# motor-control.net
KiCad netlist of a schematic drawn in Altium Designer
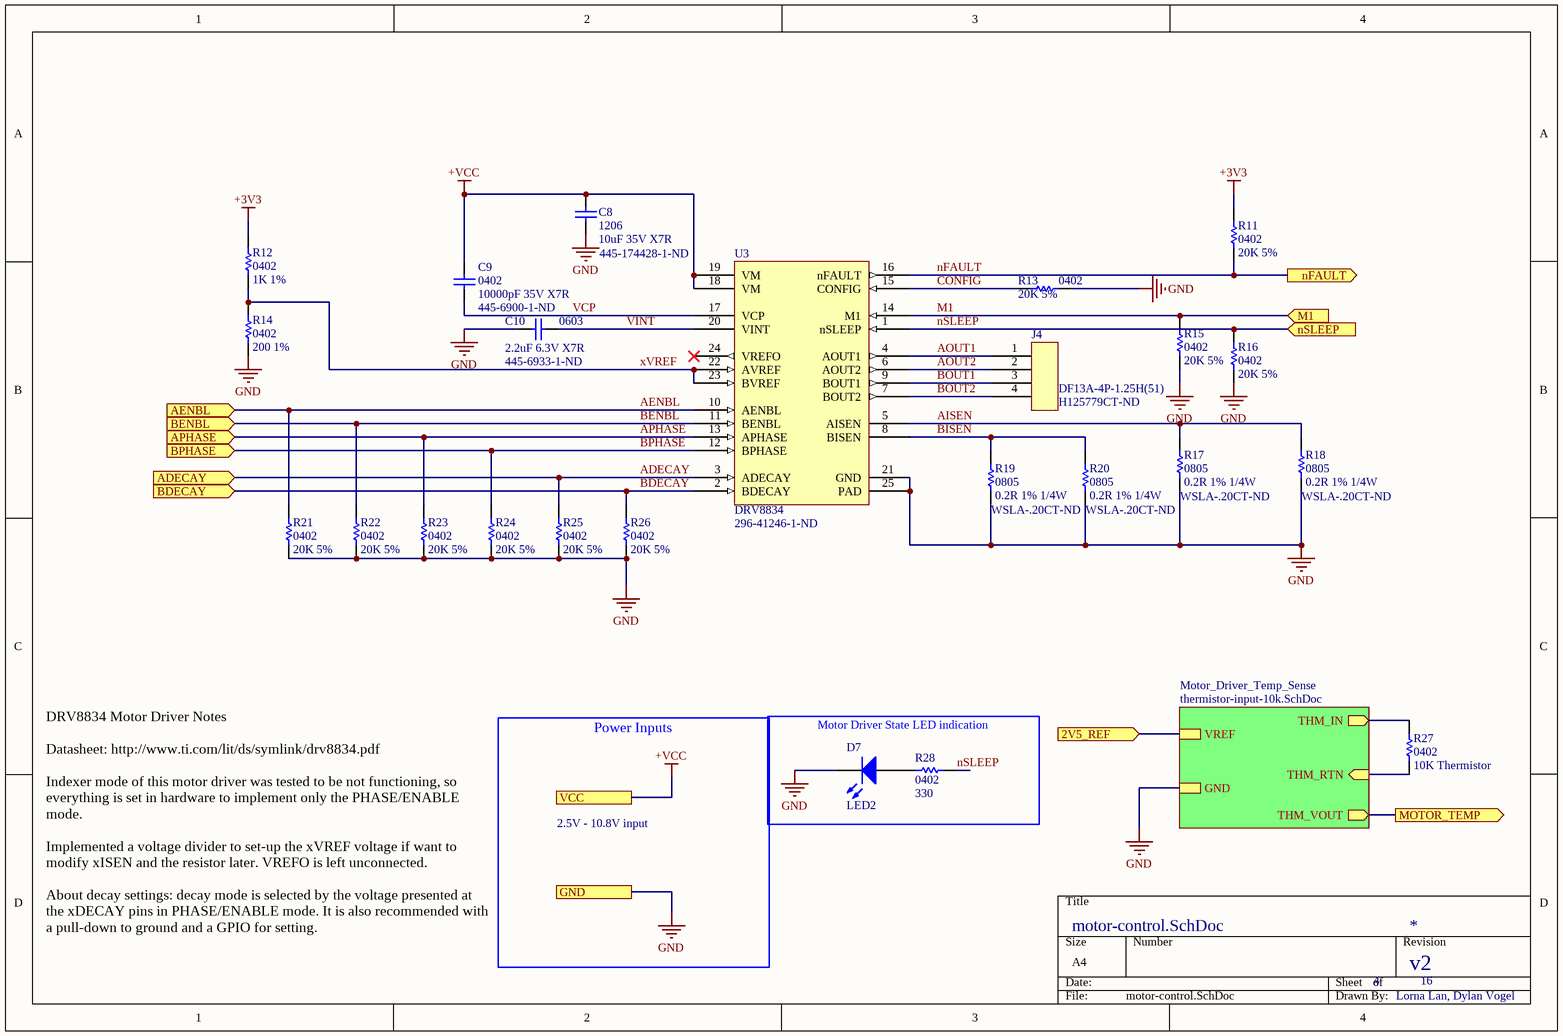
[diagram p0: motor-control.SchDoc]

(export (version "E")
  (design (tool "Eeschema 10.0.6"))
  (components
    (comp (ref "C8")
      (value "1206")
      (footprint "CAP1206R")
      (description "1206 capacitor")
      (fields
        (field (name "ALTIUM_VALUE") "10uF 35V X7R")
        (field (name "SUPPLIER PART NUMBER 1") "445-174428-1-ND")
      )
      (libsource (lib "CAP1206") (part "CAP1206"))
    )
    (comp (ref "C9")
      (value "0402")
      (footprint "CAP0402R")
      (description "0402 capacitor")
      (fields
        (field (name "ALTIUM_VALUE") "10000pF 35V X7R")
        (field (name "SUPPLIER PART NUMBER 1") "445-6900-1-ND")
      )
      (libsource (lib "CAP0402") (part "CAP0402"))
    )
    (comp (ref "C10")
      (value "0603")
      (footprint "CAP0603R")
      (description "0603 capacitor")
      (fields
        (field (name "ALTIUM_VALUE") "2.2uF 6.3V X7R")
        (field (name "SUPPLIER PART NUMBER 1") "445-6933-1-ND")
      )
      (libsource (lib "CAP0603") (part "CAP0603"))
    )
    (comp (ref "D7")
      (value "LED2")
      (footprint "0603-LED")
      (description "Typical RED, GREEN, YELLOW, AMBER GaAs LED")
      (fields (field (name "PUBLISHER") "Altium Limited"))
      (libsource (lib "Miscellaneous Devices") (part "LED2"))
    )
    (comp (ref "J4")
      (value "DF13A-4P-1.25H(51)")
      (footprint "DF13A-4P-1.25H(51)")
      (description "4 pos DF13 right angle surface mount connector")
      (fields (field (name "SUPPLIER PART NUMBER 1") "H125779CT-ND"))
      (libsource (lib "DF13A-4P-1.25H(51)") (part "DF13A-4P-1.25H(51)"))
    )
    (comp (ref "R11")
      (value "0402")
      (footprint "RES0402R")
      (description "0402 resistor")
      (fields (field (name "ALTIUM_VALUE") "20K 5%"))
      (libsource (lib "RES0402") (part "RES0402"))
    )
    (comp (ref "R12")
      (value "0402")
      (footprint "RES0402R")
      (description "0402 resistor")
      (fields (field (name "ALTIUM_VALUE") "1K 1%"))
      (libsource (lib "RES0402") (part "RES0402"))
    )
    (comp (ref "R13")
      (value "0402")
      (footprint "RES0402R")
      (description "0402 resistor")
      (fields (field (name "ALTIUM_VALUE") "20K 5%"))
      (libsource (lib "RES0402") (part "RES0402"))
    )
    (comp (ref "R14")
      (value "0402")
      (footprint "RES0402R")
      (description "0402 resistor")
      (fields (field (name "ALTIUM_VALUE") "200 1%"))
      (libsource (lib "RES0402") (part "RES0402"))
    )
    (comp (ref "R15")
      (value "0402")
      (footprint "RES0402R")
      (description "0402 resistor")
      (fields (field (name "ALTIUM_VALUE") "20K 5%"))
      (libsource (lib "RES0402") (part "RES0402"))
    )
    (comp (ref "R16")
      (value "0402")
      (footprint "RES0402R")
      (description "0402 resistor")
      (fields (field (name "ALTIUM_VALUE") "20K 5%"))
      (libsource (lib "RES0402") (part "RES0402"))
    )
    (comp (ref "R17")
      (value "0805")
      (footprint "RES0805R")
      (description "0805 resistor")
      (fields
        (field (name "ALTIUM_VALUE") "0.2R 1% 1/4W")
        (field (name "SUPPLIER PART NUMBER 1") "WSLA-.20CT-ND")
      )
      (libsource (lib "RES0805") (part "RES0805"))
    )
    (comp (ref "R18")
      (value "0805")
      (footprint "RES0805R")
      (description "0805 resistor")
      (fields
        (field (name "ALTIUM_VALUE") "0.2R 1% 1/4W")
        (field (name "SUPPLIER PART NUMBER 1") "WSLA-.20CT-ND")
      )
      (libsource (lib "RES0805") (part "RES0805"))
    )
    (comp (ref "R19")
      (value "0805")
      (footprint "RES0805R")
      (description "0805 resistor")
      (fields
        (field (name "ALTIUM_VALUE") "0.2R 1% 1/4W")
        (field (name "SUPPLIER PART NUMBER 1") "WSLA-.20CT-ND")
      )
      (libsource (lib "RES0805") (part "RES0805"))
    )
    (comp (ref "R20")
      (value "0805")
      (footprint "RES0805R")
      (description "0805 resistor")
      (fields
        (field (name "ALTIUM_VALUE") "0.2R 1% 1/4W")
        (field (name "SUPPLIER PART NUMBER 1") "WSLA-.20CT-ND")
      )
      (libsource (lib "RES0805") (part "RES0805"))
    )
    (comp (ref "R21")
      (value "0402")
      (footprint "RES0402R")
      (description "0402 resistor")
      (fields (field (name "ALTIUM_VALUE") "20K 5%"))
      (libsource (lib "RES0402") (part "RES0402"))
    )
    (comp (ref "R22")
      (value "0402")
      (footprint "RES0402R")
      (description "0402 resistor")
      (fields (field (name "ALTIUM_VALUE") "20K 5%"))
      (libsource (lib "RES0402") (part "RES0402"))
    )
    (comp (ref "R23")
      (value "0402")
      (footprint "RES0402R")
      (description "0402 resistor")
      (fields (field (name "ALTIUM_VALUE") "20K 5%"))
      (libsource (lib "RES0402") (part "RES0402"))
    )
    (comp (ref "R24")
      (value "0402")
      (footprint "RES0402R")
      (description "0402 resistor")
      (fields (field (name "ALTIUM_VALUE") "20K 5%"))
      (libsource (lib "RES0402") (part "RES0402"))
    )
    (comp (ref "R25")
      (value "0402")
      (footprint "RES0402R")
      (description "0402 resistor")
      (fields (field (name "ALTIUM_VALUE") "20K 5%"))
      (libsource (lib "RES0402") (part "RES0402"))
    )
    (comp (ref "R26")
      (value "0402")
      (footprint "RES0402R")
      (description "0402 resistor")
      (fields (field (name "ALTIUM_VALUE") "20K 5%"))
      (libsource (lib "RES0402") (part "RES0402"))
    )
    (comp (ref "R27")
      (value "0402")
      (footprint "RES0402R")
      (description "0402 resistor")
      (fields (field (name "ALTIUM_VALUE") "10K Thermistor"))
      (libsource (lib "RES0402") (part "RES0402"))
    )
    (comp (ref "R28")
      (value "0402")
      (footprint "RES0402R")
      (description "0402 resistor")
      (fields (field (name "ALTIUM_VALUE") "330"))
      (libsource (lib "RES0402") (part "RES0402"))
    )
    (comp (ref "U3")
      (value "DRV8834")
      (footprint "SOP65P640X120-25N")
      (description "Dual-bridge stepper or dc motor driver. 1.5A per coil with 2.5-10.8 V load supply.")
      (fields (field (name "SUPPLIER PART NUMBER 1") "296-41246-1-ND"))
      (libsource (lib "DRV8834") (part "DRV8834"))
    )
  )
  (nets
    (net (code "1") (name "+3V3") (class "Default")
      (node (ref "R11") (pin "2") (pinfunction "2_2") (pintype "passive"))
      (node (ref "R12") (pin "2") (pinfunction "2_2") (pintype "passive"))
    )
    (net (code "2") (name "+VCC") (class "Default")
      (node (ref "C8") (pin "2") (pinfunction "2_2") (pintype "passive"))
      (node (ref "C9") (pin "2") (pinfunction "2_2") (pintype "passive"))
      (node (ref "U3") (pin "18") (pinfunction "VM_18") (pintype "power_in"))
      (node (ref "U3") (pin "19") (pinfunction "VM_19") (pintype "power_in"))
    )
    (net (code "4") (name "/ADECAY") (class "Default")
      (node (ref "R25") (pin "2") (pinfunction "2_2") (pintype "passive"))
      (node (ref "U3") (pin "3") (pinfunction "ADECAY_3") (pintype "input"))
    )
    (net (code "5") (name "/AENBL") (class "Default")
      (node (ref "R21") (pin "2") (pinfunction "2_2") (pintype "passive"))
      (node (ref "U3") (pin "10") (pinfunction "AENBL_10") (pintype "input"))
    )
    (net (code "6") (name "/AISEN") (class "Default")
      (node (ref "R17") (pin "2") (pinfunction "2_2") (pintype "passive"))
      (node (ref "R18") (pin "2") (pinfunction "2_2") (pintype "passive"))
      (node (ref "U3") (pin "5") (pinfunction "AISEN_5") (pintype "passive"))
    )
    (net (code "7") (name "/AOUT1") (class "Default")
      (node (ref "J4") (pin "1") (pintype "passive"))
      (node (ref "U3") (pin "4") (pinfunction "AOUT1_4") (pintype "output"))
    )
    (net (code "8") (name "/AOUT2") (class "Default")
      (node (ref "J4") (pin "2") (pintype "passive"))
      (node (ref "U3") (pin "6") (pinfunction "AOUT2_6") (pintype "output"))
    )
    (net (code "9") (name "/APHASE") (class "Default")
      (node (ref "R23") (pin "2") (pinfunction "2_2") (pintype "passive"))
      (node (ref "U3") (pin "13") (pinfunction "APHASE_13") (pintype "input"))
    )
    (net (code "10") (name "/BDECAY") (class "Default")
      (node (ref "R26") (pin "2") (pinfunction "2_2") (pintype "passive"))
      (node (ref "U3") (pin "2") (pinfunction "BDECAY_2") (pintype "input"))
    )
    (net (code "11") (name "/BENBL") (class "Default")
      (node (ref "R22") (pin "2") (pinfunction "2_2") (pintype "passive"))
      (node (ref "U3") (pin "11") (pinfunction "BENBL_11") (pintype "input"))
    )
    (net (code "12") (name "/BISEN") (class "Default")
      (node (ref "R19") (pin "2") (pinfunction "2_2") (pintype "passive"))
      (node (ref "R20") (pin "2") (pinfunction "2_2") (pintype "passive"))
      (node (ref "U3") (pin "8") (pinfunction "BISEN_8") (pintype "passive"))
    )
    (net (code "13") (name "/BOUT1") (class "Default")
      (node (ref "J4") (pin "3") (pintype "passive"))
      (node (ref "U3") (pin "9") (pinfunction "BOUT1_9") (pintype "output"))
    )
    (net (code "14") (name "/BOUT2") (class "Default")
      (node (ref "J4") (pin "4") (pintype "passive"))
      (node (ref "U3") (pin "7") (pinfunction "BOUT2_7") (pintype "output"))
    )
    (net (code "15") (name "/BPHASE") (class "Default")
      (node (ref "R24") (pin "2") (pinfunction "2_2") (pintype "passive"))
      (node (ref "U3") (pin "12") (pinfunction "BPHASE_12") (pintype "input"))
    )
    (net (code "16") (name "/CONFIG") (class "Default")
      (node (ref "R13") (pin "2") (pinfunction "2_2") (pintype "passive"))
      (node (ref "U3") (pin "15") (pinfunction "CONFIG_15") (pintype "input"))
    )
    (net (code "17") (name "/M1") (class "Default")
      (node (ref "R15") (pin "2") (pinfunction "2_2") (pintype "passive"))
      (node (ref "U3") (pin "14") (pinfunction "M1_14") (pintype "input"))
    )
    (net (code "19") (name "/THM_IN") (class "Default")
      (node (ref "R27") (pin "2") (pinfunction "2_2") (pintype "passive"))
    )
    (net (code "20") (name "/THM_RTN") (class "Default")
      (node (ref "R27") (pin "1") (pinfunction "1_1") (pintype "passive"))
    )
    (net (code "21") (name "/VCP") (class "Default")
      (node (ref "C9") (pin "1") (pinfunction "1_1") (pintype "passive"))
      (node (ref "U3") (pin "17") (pinfunction "VCP_17") (pintype "power_in"))
    )
    (net (code "22") (name "/VINT") (class "Default")
      (node (ref "C10") (pin "1") (pinfunction "1_1") (pintype "passive"))
      (node (ref "U3") (pin "20") (pinfunction "VINT_20") (pintype "power_in"))
    )
    (net (code "23") (name "/nFAULT") (class "Default")
      (node (ref "R11") (pin "1") (pinfunction "1_1") (pintype "passive"))
      (node (ref "U3") (pin "16") (pinfunction "nFAULT_16") (pintype "output"))
    )
    (net (code "24") (name "/nSLEEP") (class "Default")
      (node (ref "R16") (pin "2") (pinfunction "2_2") (pintype "passive"))
      (node (ref "R28") (pin "1") (pinfunction "1_1") (pintype "passive"))
      (node (ref "U3") (pin "1") (pinfunction "nSLEEP_1") (pintype "input"))
    )
    (net (code "25") (name "/xVREF") (class "Default")
      (node (ref "R12") (pin "1") (pinfunction "1_1") (pintype "passive"))
      (node (ref "R14") (pin "2") (pinfunction "2_2") (pintype "passive"))
      (node (ref "U3") (pin "22") (pinfunction "AVREF_22") (pintype "input"))
      (node (ref "U3") (pin "23") (pinfunction "BVREF_23") (pintype "input"))
    )
    (net (code "26") (name "GND") (class "Default")
      (node (ref "C10") (pin "2") (pinfunction "2_2") (pintype "passive"))
      (node (ref "C8") (pin "1") (pinfunction "1_1") (pintype "passive"))
      (node (ref "D7") (pin "2") (pinfunction "K_2") (pintype "passive"))
      (node (ref "R13") (pin "1") (pinfunction "1_1") (pintype "passive"))
      (node (ref "R14") (pin "1") (pinfunction "1_1") (pintype "passive"))
      (node (ref "R15") (pin "1") (pinfunction "1_1") (pintype "passive"))
      (node (ref "R16") (pin "1") (pinfunction "1_1") (pintype "passive"))
      (node (ref "R17") (pin "1") (pinfunction "1_1") (pintype "passive"))
      (node (ref "R18") (pin "1") (pinfunction "1_1") (pintype "passive"))
      (node (ref "R19") (pin "1") (pinfunction "1_1") (pintype "passive"))
      (node (ref "R20") (pin "1") (pinfunction "1_1") (pintype "passive"))
      (node (ref "R21") (pin "1") (pinfunction "1_1") (pintype "passive"))
      (node (ref "R22") (pin "1") (pinfunction "1_1") (pintype "passive"))
      (node (ref "R23") (pin "1") (pinfunction "1_1") (pintype "passive"))
      (node (ref "R24") (pin "1") (pinfunction "1_1") (pintype "passive"))
      (node (ref "R25") (pin "1") (pinfunction "1_1") (pintype "passive"))
      (node (ref "R26") (pin "1") (pinfunction "1_1") (pintype "passive"))
      (node (ref "U3") (pin "21") (pinfunction "GND_21") (pintype "power_in"))
      (node (ref "U3") (pin "25") (pinfunction "PAD_25") (pintype "power_in"))
    )
    (net (code "27") (name "Net-(D7-A)") (class "Default")
      (node (ref "D7") (pin "1") (pinfunction "A_1") (pintype "passive"))
      (node (ref "R28") (pin "2") (pinfunction "2_2") (pintype "passive"))
    )
    (net (code "28") (name "unconnected-(U3-VREFO-Pad24)") (class "Default")
      (node (ref "U3") (pin "24") (pinfunction "VREFO_24") (pintype "output+no_connect"))
    )
  )
)
